# GeigerChannel.net
KiCad netlist of a schematic drawn in Altium Designer
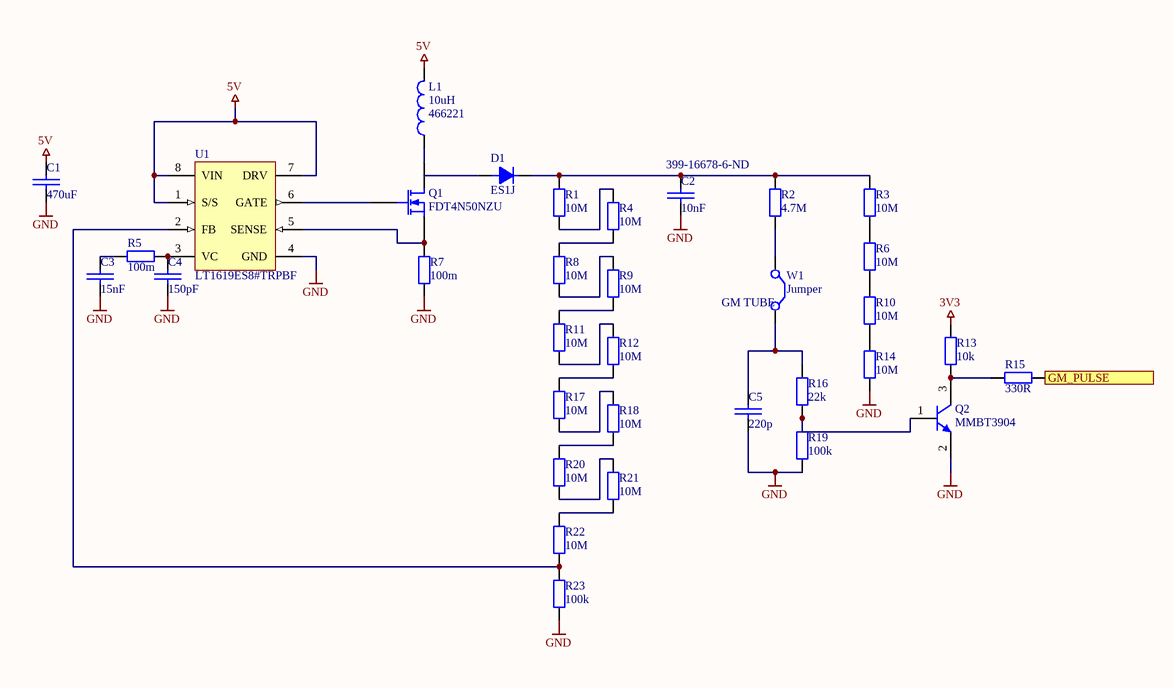
[diagram p0: GeigerChannel.SchDoc]

(export (version "E")
  (design (tool "Eeschema 10.0.6"))
  (components
    (comp (ref "C1") (value "470uF") (footprint "Cap_0805") (libsource (lib "*") (part "C")))
    (comp (ref "C2")
      (value "10nF")
      (footprint "1206")
      (fields (field (name "SUPPLIER PART NUMBER 1") "399-16678-6-ND"))
      (libsource (lib "*") (part "C"))
    )
    (comp (ref "C3") (value "15nF") (footprint "Cap_0805") (libsource (lib "*") (part "C")))
    (comp (ref "C4") (value "150pF") (footprint "Cap_0805") (libsource (lib "*") (part "C")))
    (comp (ref "C5") (value "220p") (footprint "1206") (libsource (lib "*") (part "C")))
    (comp (ref "D1")
      (value "ES1J")
      (footprint "DIOM5227X250N")
      (description "Ð”Ð¸Ð¾Ð´, ÑÐ²ÐµÑ€Ñ…Ð±Ñ‹ÑÑ‚Ñ€Ñ‹Ð¹, SMA, 600 Ð’, 1 Ð, 35 Ð½Ñ, 150 Â°C")
      (fields (field (name "MF") "Diotec Semiconductor"))
      (libsource (lib "AZR-LIB") (part "ES1J"))
    )
    (comp (ref "L1")
      (value "10uH")
      (footprint "SRN3015C")
      (description "Inductor")
      (fields (field (name "SUPPLIER PART NUMBER 1") "466221") (field (name "PUBLISHER") "Altium Limited"))
      (libsource (lib "Miscellaneous Devices") (part "Inductor"))
    )
    (comp (ref "Q1")
      (value "FDT4N50NZU")
      (footprint "SOT-223")
      (libsource (lib "AZR-LIB") (part "FDT4N50NZU"))
    )
    (comp (ref "Q2")
      (value "MMBT3904")
      (footprint "FAIR-SOT23-3_V")
      (description "NPN General Purpose Amplifier, 40 V, 0.2 A, -55 to 150 degC, 3-Pin SOT23, RoHS, Tape and Reel")
      (fields (field (name "TOLERANCE") "30ppm"))
      (libsource (lib "Altium Content Vault") (part "BJT-NPN-BEC-3"))
    )
    (comp (ref "R1")
      (value "10M")
      (footprint "RES_0805")
      (description "Res 0805")
      (fields (field (name "PART NUMBER") "ERJ6ENF2703V") (field (name "MANUFACTURER") "Panasonic"))
      (libsource (lib "") (part "RES_1"))
    )
    (comp (ref "R2")
      (value "4.7M")
      (footprint "RES_0805")
      (description "Res 0805")
      (fields (field (name "PART NUMBER") "ERJ6ENF2703V") (field (name "MANUFACTURER") "Panasonic"))
      (libsource (lib "") (part "RES_1"))
    )
    (comp (ref "R3")
      (value "10M")
      (footprint "RES_0805")
      (description "Res 0805")
      (fields (field (name "PART NUMBER") "ERJ6ENF2703V") (field (name "MANUFACTURER") "Panasonic"))
      (libsource (lib "") (part "RES_1"))
    )
    (comp (ref "R4")
      (value "10M")
      (footprint "RES_0805")
      (description "Res 0805")
      (fields (field (name "PART NUMBER") "ERJ6ENF2703V") (field (name "MANUFACTURER") "Panasonic"))
      (libsource (lib "") (part "RES_1"))
    )
    (comp (ref "R5")
      (value "100m")
      (footprint "RES_0805")
      (description "Res 0805")
      (fields (field (name "PART NUMBER") "ERJ6ENF2703V") (field (name "MANUFACTURER") "Panasonic"))
      (libsource (lib "2121_Robot3roues_V2.0") (part "RES"))
    )
    (comp (ref "R6")
      (value "10M")
      (footprint "RES_0805")
      (description "Res 0805")
      (fields (field (name "PART NUMBER") "ERJ6ENF2703V") (field (name "MANUFACTURER") "Panasonic"))
      (libsource (lib "") (part "RES_1"))
    )
    (comp (ref "R7")
      (value "100m")
      (footprint "RES_0805")
      (description "Res 0805")
      (fields (field (name "PART NUMBER") "ERJ6ENF2703V") (field (name "MANUFACTURER") "Panasonic"))
      (libsource (lib "") (part "RES_1"))
    )
    (comp (ref "R8")
      (value "10M")
      (footprint "RES_0805")
      (description "Res 0805")
      (fields (field (name "PART NUMBER") "ERJ6ENF2703V") (field (name "MANUFACTURER") "Panasonic"))
      (libsource (lib "") (part "RES_1"))
    )
    (comp (ref "R9")
      (value "10M")
      (footprint "RES_0805")
      (description "Res 0805")
      (fields (field (name "PART NUMBER") "ERJ6ENF2703V") (field (name "MANUFACTURER") "Panasonic"))
      (libsource (lib "") (part "RES_1"))
    )
    (comp (ref "R10")
      (value "10M")
      (footprint "RES_0805")
      (description "Res 0805")
      (fields (field (name "PART NUMBER") "ERJ6ENF2703V") (field (name "MANUFACTURER") "Panasonic"))
      (libsource (lib "") (part "RES_1"))
    )
    (comp (ref "R11")
      (value "10M")
      (footprint "RES_0805")
      (description "Res 0805")
      (fields (field (name "PART NUMBER") "ERJ6ENF2703V") (field (name "MANUFACTURER") "Panasonic"))
      (libsource (lib "") (part "RES_1"))
    )
    (comp (ref "R12")
      (value "10M")
      (footprint "RES_0805")
      (description "Res 0805")
      (fields (field (name "PART NUMBER") "ERJ6ENF2703V") (field (name "MANUFACTURER") "Panasonic"))
      (libsource (lib "") (part "RES_1"))
    )
    (comp (ref "R13")
      (value "10k")
      (footprint "RES_0805")
      (description "Res 0805")
      (fields (field (name "PART NUMBER") "ERJ6ENF2703V") (field (name "MANUFACTURER") "Panasonic"))
      (libsource (lib "") (part "RES_1"))
    )
    (comp (ref "R14")
      (value "10M")
      (footprint "RES_0805")
      (description "Res 0805")
      (fields (field (name "PART NUMBER") "ERJ6ENF2703V") (field (name "MANUFACTURER") "Panasonic"))
      (libsource (lib "") (part "RES_1"))
    )
    (comp (ref "R15")
      (value "330R")
      (footprint "RES_0805")
      (description "Res 0805")
      (fields (field (name "PART NUMBER") "ERJ6ENF2703V") (field (name "MANUFACTURER") "Panasonic"))
      (libsource (lib "2121_Robot3roues_V2.0") (part "RES"))
    )
    (comp (ref "R16")
      (value "22k")
      (footprint "RES_0805")
      (description "Res 0805")
      (fields (field (name "PART NUMBER") "ERJ6ENF2703V") (field (name "MANUFACTURER") "Panasonic"))
      (libsource (lib "") (part "RES_1"))
    )
    (comp (ref "R17")
      (value "10M")
      (footprint "RES_0805")
      (description "Res 0805")
      (fields (field (name "PART NUMBER") "ERJ6ENF2703V") (field (name "MANUFACTURER") "Panasonic"))
      (libsource (lib "") (part "RES_1"))
    )
    (comp (ref "R18")
      (value "10M")
      (footprint "RES_0805")
      (description "Res 0805")
      (fields (field (name "PART NUMBER") "ERJ6ENF2703V") (field (name "MANUFACTURER") "Panasonic"))
      (libsource (lib "") (part "RES_1"))
    )
    (comp (ref "R19")
      (value "100k")
      (footprint "RES_0805")
      (description "Res 0805")
      (fields (field (name "PART NUMBER") "ERJ6ENF2703V") (field (name "MANUFACTURER") "Panasonic"))
      (libsource (lib "") (part "RES_1"))
    )
    (comp (ref "R20")
      (value "10M")
      (footprint "RES_0805")
      (description "Res 0805")
      (fields (field (name "PART NUMBER") "ERJ6ENF2703V") (field (name "MANUFACTURER") "Panasonic"))
      (libsource (lib "") (part "RES_1"))
    )
    (comp (ref "R21")
      (value "10M")
      (footprint "RES_0805")
      (description "Res 0805")
      (fields (field (name "PART NUMBER") "ERJ6ENF2703V") (field (name "MANUFACTURER") "Panasonic"))
      (libsource (lib "") (part "RES_1"))
    )
    (comp (ref "R22")
      (value "10M")
      (footprint "RES_0805")
      (description "Res 0805")
      (fields (field (name "PART NUMBER") "ERJ6ENF2703V") (field (name "MANUFACTURER") "Panasonic"))
      (libsource (lib "") (part "RES_1"))
    )
    (comp (ref "R23")
      (value "100k")
      (footprint "RES_0805")
      (description "Res 0805")
      (fields (field (name "PART NUMBER") "ERJ6ENF2703V") (field (name "MANUFACTURER") "Panasonic"))
      (libsource (lib "") (part "RES_1"))
    )
    (comp (ref "U1")
      (value "LT1619ES8#TRPBF")
      (footprint "LT-S8-8_N")
      (description "Low Voltage Current Mode PWM Controller, 8-pin SOIC (S8-8), -40 to 85 degC, Pb-Free, Tape and Reel")
      (fields (field (name "MANUFACTURER") "Linear Technology"))
      (libsource (lib "Altium Content Vault") (part "LT-LT1619-8"))
    )
    (comp (ref "W1")
      (value "Jumper")
      (footprint "RAD-0.2")
      (description "Jumper Wire")
      (fields (field (name "PUBLISHER") "Altium Limited"))
      (libsource (lib "Miscellaneous Devices") (part "Jumper"))
    )
  )
  (nets
    (net (code "1") (name "/GM_PULSE") (class "Default")
      (node (ref "R15") (pin "2") (pinfunction "2_2") (pintype "passive"))
    )
    (net (code "2") (name "3V3") (class "Default")
      (node (ref "R13") (pin "1") (pinfunction "1_1") (pintype "passive"))
    )
    (net (code "3") (name "5V") (class "Default")
      (node (ref "C1") (pin "1") (pinfunction "1_1") (pintype "passive"))
      (node (ref "L1") (pin "2") (pinfunction "2_2") (pintype "passive"))
      (node (ref "U1") (pin "1") (pinfunction "S/S_1") (pintype "input"))
      (node (ref "U1") (pin "7") (pinfunction "DRV_7") (pintype "power_in"))
      (node (ref "U1") (pin "8") (pinfunction "VIN_8") (pintype "power_in"))
    )
    (net (code "4") (name "GND") (class "Default")
      (node (ref "C1") (pin "2") (pinfunction "2_2") (pintype "passive"))
      (node (ref "C2") (pin "2") (pinfunction "2_2") (pintype "passive"))
      (node (ref "C3") (pin "2") (pinfunction "2_2") (pintype "passive"))
      (node (ref "C4") (pin "2") (pinfunction "2_2") (pintype "passive"))
      (node (ref "C5") (pin "2") (pinfunction "2_2") (pintype "passive"))
      (node (ref "Q2") (pin "2") (pinfunction "E_2") (pintype "passive"))
      (node (ref "R14") (pin "2") (pinfunction "2_2") (pintype "passive"))
      (node (ref "R19") (pin "2") (pinfunction "2_2") (pintype "passive"))
      (node (ref "R23") (pin "2") (pinfunction "2_2") (pintype "passive"))
      (node (ref "R7") (pin "2") (pinfunction "2_2") (pintype "passive"))
      (node (ref "U1") (pin "4") (pinfunction "GND_4") (pintype "power_in"))
    )
    (net (code "5") (name "Net-(C3-Pad1)") (class "Default")
      (node (ref "C3") (pin "1") (pinfunction "1_1") (pintype "passive"))
      (node (ref "R5") (pin "1") (pinfunction "1_1") (pintype "passive"))
    )
    (net (code "6") (name "Net-(D1-A)") (class "Default")
      (node (ref "C2") (pin "1") (pinfunction "1_1") (pintype "passive"))
      (node (ref "D1") (pin "1") (pinfunction "A_1") (pintype "passive"))
      (node (ref "R1") (pin "1") (pinfunction "1_1") (pintype "passive"))
      (node (ref "R2") (pin "1") (pinfunction "1_1") (pintype "passive"))
      (node (ref "R3") (pin "1") (pinfunction "1_1") (pintype "passive"))
    )
    (net (code "7") (name "Net-(L1-Pad1)") (class "Default")
      (node (ref "L1") (pin "1") (pinfunction "1_1") (pintype "passive"))
      (node (ref "Q1") (pin "D") (pinfunction "D_D") (pintype "passive"))
    )
    (net (code "8") (name "Net-(Q2-B)") (class "Default")
      (node (ref "Q2") (pin "1") (pinfunction "B_1") (pintype "passive"))
      (node (ref "R16") (pin "2") (pinfunction "2_2") (pintype "passive"))
      (node (ref "R19") (pin "1") (pinfunction "1_1") (pintype "passive"))
    )
    (net (code "9") (name "Net-(Q2-C)") (class "Default")
      (node (ref "Q2") (pin "3") (pinfunction "C_3") (pintype "passive"))
      (node (ref "R13") (pin "2") (pinfunction "2_2") (pintype "passive"))
      (node (ref "R15") (pin "1") (pinfunction "1_1") (pintype "passive"))
    )
    (net (code "10") (name "Net-(R1-Pad2)") (class "Default")
      (node (ref "R1") (pin "2") (pinfunction "2_2") (pintype "passive"))
      (node (ref "R4") (pin "1") (pinfunction "1_1") (pintype "passive"))
    )
    (net (code "11") (name "Net-(R3-Pad2)") (class "Default")
      (node (ref "R3") (pin "2") (pinfunction "2_2") (pintype "passive"))
      (node (ref "R6") (pin "1") (pinfunction "1_1") (pintype "passive"))
    )
    (net (code "12") (name "Net-(R4-Pad2)") (class "Default")
      (node (ref "R4") (pin "2") (pinfunction "2_2") (pintype "passive"))
      (node (ref "R8") (pin "1") (pinfunction "1_1") (pintype "passive"))
    )
    (net (code "13") (name "Net-(R8-Pad2)") (class "Default")
      (node (ref "R8") (pin "2") (pinfunction "2_2") (pintype "passive"))
      (node (ref "R9") (pin "1") (pinfunction "1_1") (pintype "passive"))
    )
    (net (code "14") (name "Net-(R10-Pad1)") (class "Default")
      (node (ref "R10") (pin "1") (pinfunction "1_1") (pintype "passive"))
      (node (ref "R6") (pin "2") (pinfunction "2_2") (pintype "passive"))
    )
    (net (code "15") (name "Net-(R10-Pad2)") (class "Default")
      (node (ref "R10") (pin "2") (pinfunction "2_2") (pintype "passive"))
      (node (ref "R14") (pin "1") (pinfunction "1_1") (pintype "passive"))
    )
    (net (code "16") (name "Net-(R11-Pad1)") (class "Default")
      (node (ref "R11") (pin "1") (pinfunction "1_1") (pintype "passive"))
      (node (ref "R9") (pin "2") (pinfunction "2_2") (pintype "passive"))
    )
    (net (code "17") (name "Net-(R11-Pad2)") (class "Default")
      (node (ref "R11") (pin "2") (pinfunction "2_2") (pintype "passive"))
      (node (ref "R12") (pin "1") (pinfunction "1_1") (pintype "passive"))
    )
    (net (code "18") (name "Net-(R12-Pad2)") (class "Default")
      (node (ref "R12") (pin "2") (pinfunction "2_2") (pintype "passive"))
      (node (ref "R17") (pin "1") (pinfunction "1_1") (pintype "passive"))
    )
    (net (code "19") (name "Net-(R17-Pad2)") (class "Default")
      (node (ref "R17") (pin "2") (pinfunction "2_2") (pintype "passive"))
      (node (ref "R18") (pin "1") (pinfunction "1_1") (pintype "passive"))
    )
    (net (code "20") (name "Net-(R18-Pad2)") (class "Default")
      (node (ref "R18") (pin "2") (pinfunction "2_2") (pintype "passive"))
      (node (ref "R20") (pin "1") (pinfunction "1_1") (pintype "passive"))
    )
    (net (code "21") (name "Net-(R20-Pad2)") (class "Default")
      (node (ref "R20") (pin "2") (pinfunction "2_2") (pintype "passive"))
      (node (ref "R21") (pin "1") (pinfunction "1_1") (pintype "passive"))
    )
    (net (code "22") (name "Net-(R21-Pad2)") (class "Default")
      (node (ref "R21") (pin "2") (pinfunction "2_2") (pintype "passive"))
      (node (ref "R22") (pin "1") (pinfunction "1_1") (pintype "passive"))
    )
    (net (code "23") (name "Net-(U1-FB)") (class "Default")
      (node (ref "R22") (pin "2") (pinfunction "2_2") (pintype "passive"))
      (node (ref "R23") (pin "1") (pinfunction "1_1") (pintype "passive"))
      (node (ref "U1") (pin "2") (pinfunction "FB_2") (pintype "input"))
    )
    (net (code "24") (name "Net-(U1-GATE)") (class "Default")
      (node (ref "Q1") (pin "G") (pinfunction "G_G") (pintype "passive"))
      (node (ref "U1") (pin "6") (pinfunction "GATE_6") (pintype "output"))
    )
    (net (code "25") (name "Net-(U1-SENSE)") (class "Default")
      (node (ref "Q1") (pin "S") (pinfunction "S_S") (pintype "passive"))
      (node (ref "R7") (pin "1") (pinfunction "1_1") (pintype "passive"))
      (node (ref "U1") (pin "5") (pinfunction "SENSE_5") (pintype "input"))
    )
    (net (code "26") (name "Net-(U1-VC)") (class "Default")
      (node (ref "C4") (pin "1") (pinfunction "1_1") (pintype "passive"))
      (node (ref "R5") (pin "2") (pinfunction "2_2") (pintype "passive"))
      (node (ref "U1") (pin "3") (pinfunction "VC_3") (pintype "passive"))
    )
    (net (code "27") (name "Net-(W1-C1)") (class "Default")
      (node (ref "R2") (pin "2") (pinfunction "2_2") (pintype "passive"))
      (node (ref "W1") (pin "1") (pinfunction "C1_1") (pintype "passive"))
    )
    (net (code "28") (name "Net-(W1-C2)") (class "Default")
      (node (ref "C5") (pin "1") (pinfunction "1_1") (pintype "passive"))
      (node (ref "R16") (pin "1") (pinfunction "1_1") (pintype "passive"))
      (node (ref "W1") (pin "2") (pinfunction "C2_2") (pintype "passive"))
    )
    (net (code "29") (name "unconnected-(D1-B-Pad2)") (class "Default")
      (node (ref "D1") (pin "2") (pinfunction "B_2") (pintype "passive"))
    )
  )
)
